# Main.net
KiCad netlist of a schematic drawn in Altium Designer
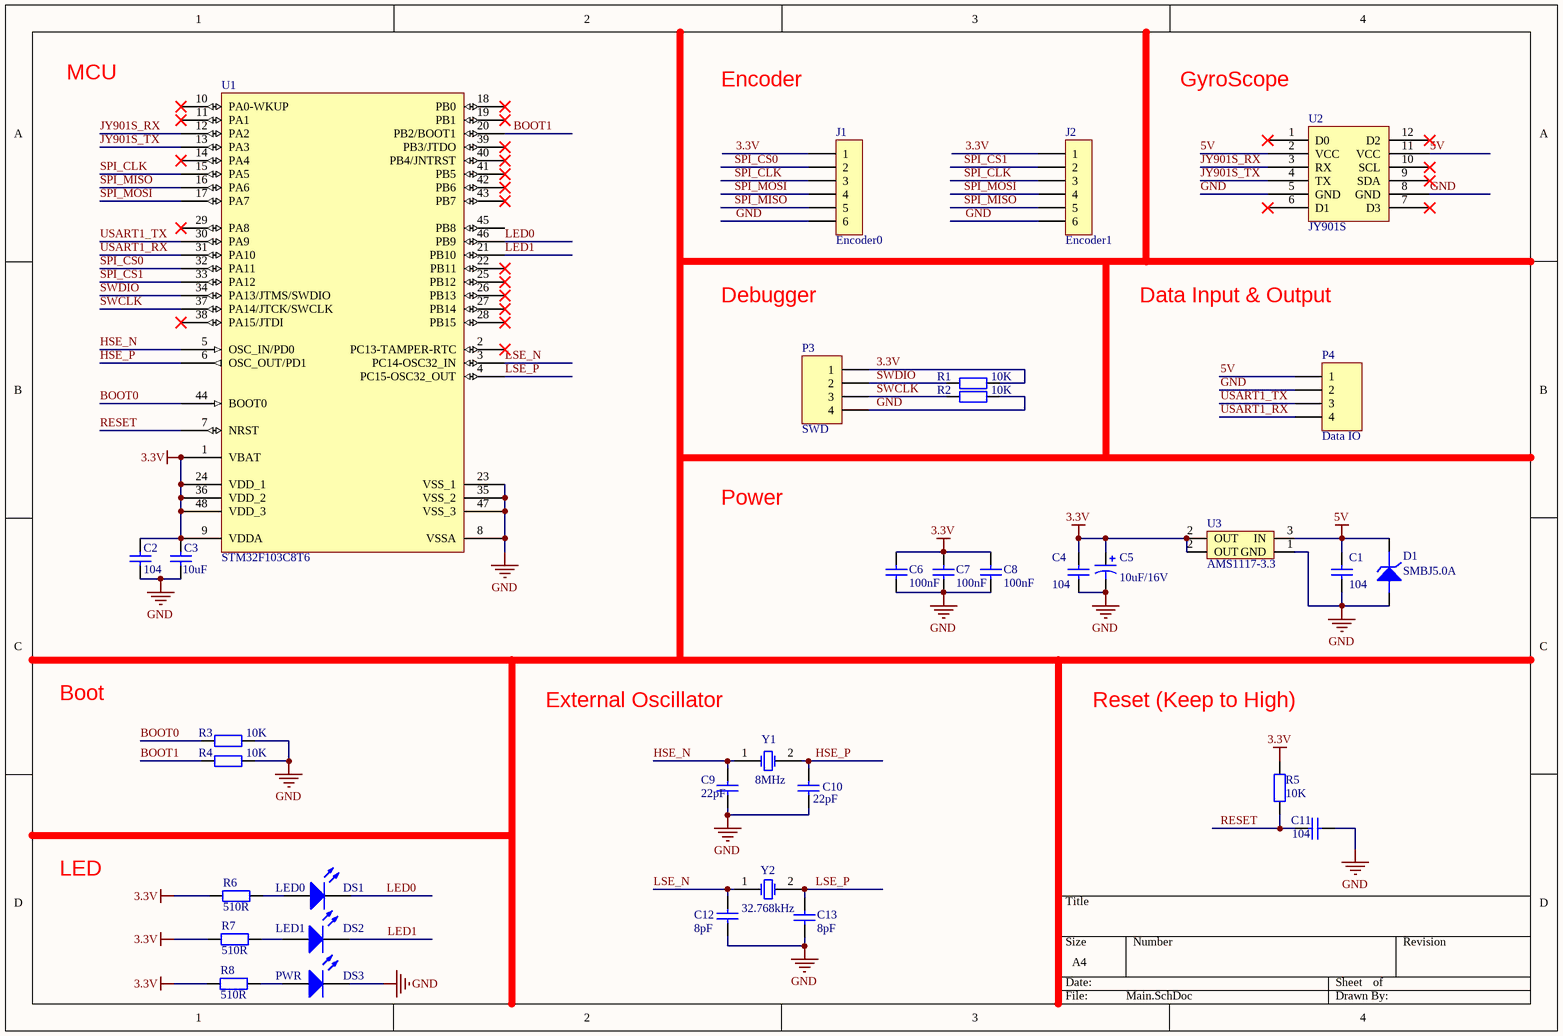
[diagram p0: Main.SchDoc]

(export (version "E")
  (design (tool "Eeschema 10.0.6"))
  (components
    (comp (ref "C1")
      (value "104")
      (footprint "0603C")
      (description "Capacitor")
      (fields (field (name "PUBLISHER") "Altium Limited"))
      (libsource (lib "prj-schlib") (part "Cap"))
    )
    (comp (ref "C2")
      (value "104")
      (footprint "0603C")
      (description "Capacitor")
      (fields (field (name "PUBLISHER") "Altium Limited"))
      (libsource (lib "prj-schlib") (part "Cap"))
    )
    (comp (ref "C3")
      (value "10uF")
      (footprint "0603C")
      (description "Capacitor")
      (fields (field (name "PUBLISHER") "Altium Limited"))
      (libsource (lib "prj-schlib") (part "Cap"))
    )
    (comp (ref "C4")
      (value "104")
      (footprint "0603C")
      (description "Capacitor")
      (fields (field (name "PUBLISHER") "Altium Limited"))
      (libsource (lib "prj-schlib") (part "Cap"))
    )
    (comp (ref "C5")
      (value "10uF/16V")
      (footprint "TAJ-A/3216")
      (description "Polarized Capacitor (Radial)")
      (fields (field (name "Comment") "Capacitor") (field (name "PUBLISHER") "Altium Limited"))
      (libsource (lib "prj-schlib") (part "Cap Pol1"))
    )
    (comp (ref "C6")
      (value "100nF")
      (footprint "0603C")
      (description "Capacitor")
      (fields (field (name "PUBLISHER") "Altium Limited"))
      (libsource (lib "prj-schlib") (part "Cap"))
    )
    (comp (ref "C7")
      (value "100nF")
      (footprint "0603C")
      (description "Capacitor")
      (fields (field (name "PUBLISHER") "Altium Limited"))
      (libsource (lib "prj-schlib") (part "Cap"))
    )
    (comp (ref "C8")
      (value "100nF")
      (footprint "0603C")
      (description "Capacitor")
      (fields (field (name "PUBLISHER") "Altium Limited"))
      (libsource (lib "prj-schlib") (part "Cap"))
    )
    (comp (ref "C9")
      (value "22pF")
      (footprint "0603C")
      (description "Capacitor")
      (fields (field (name "PUBLISHER") "Altium Limited"))
      (libsource (lib "prj-schlib") (part "Cap"))
    )
    (comp (ref "C10")
      (value "22pF")
      (footprint "0603C")
      (description "Capacitor")
      (fields (field (name "PUBLISHER") "Altium Limited"))
      (libsource (lib "prj-schlib") (part "Cap"))
    )
    (comp (ref "C11")
      (value "104")
      (footprint "0603C")
      (description "Capacitor")
      (fields (field (name "PUBLISHER") "Altium Limited"))
      (libsource (lib "prj-schlib") (part "Cap"))
    )
    (comp (ref "C12")
      (value "8pF")
      (footprint "0603C")
      (description "Capacitor")
      (fields (field (name "PUBLISHER") "Altium Limited"))
      (libsource (lib "prj-schlib") (part "Cap"))
    )
    (comp (ref "C13")
      (value "8pF")
      (footprint "0603C")
      (description "Capacitor")
      (fields (field (name "PUBLISHER") "Altium Limited"))
      (libsource (lib "prj-schlib") (part "Cap"))
    )
    (comp (ref "D1")
      (value "SMBJ5.0A")
      (footprint "SMB/DO-214AA")
      (description "稳压二极管")
      (fields (field (name "Comment") "TVS Diode"))
      (libsource (lib "prj-schlib") (part "DIODE ZENER"))
    )
    (comp (ref "DS1")
      (value "LED0")
      (footprint "LED-0805R")
      (description "Typical RED GaAs LED")
      (fields (field (name "PUBLISHER") "Altium Limited"))
      (libsource (lib "prj-schlib") (part "LED1"))
    )
    (comp (ref "DS2")
      (value "LED1")
      (footprint "LED-0805R")
      (description "Typical RED GaAs LED")
      (fields (field (name "PUBLISHER") "Altium Limited"))
      (libsource (lib "prj-schlib") (part "LED1"))
    )
    (comp (ref "DS3")
      (value "PWR")
      (footprint "LED-0805R")
      (description "Typical RED GaAs LED")
      (fields (field (name "PUBLISHER") "Altium Limited"))
      (libsource (lib "prj-schlib") (part "LED1"))
    )
    (comp (ref "J1") (value "Encoder0") (footprint "6P_SMD") (libsource (lib "prj-schlib") (part "Header 6")))
    (comp (ref "J2") (value "Encoder1") (footprint "6P_SMD") (libsource (lib "prj-schlib") (part "Header 6")))
    (comp (ref "P3")
      (value "SWD")
      (footprint "Pin HDR1X4/2.54mm-S")
      (description "Header, 4-Pin")
      (fields (field (name "PUBLISHER") "Altium Limited"))
      (libsource (lib "prj-schlib") (part "Header 4"))
    )
    (comp (ref "P4")
      (value "Data IO")
      (footprint "XH4/2.54mm/180")
      (description "Header, 4-Pin")
      (fields (field (name "PUBLISHER") "Altium Limited"))
      (libsource (lib "") (part "Header 4_1"))
    )
    (comp (ref "R1")
      (value "10K")
      (footprint "0603R")
      (description "Resistor")
      (fields (field (name "PUBLISHER") "Altium Limited"))
      (libsource (lib "prj-schlib") (part "Res2"))
    )
    (comp (ref "R2")
      (value "10K")
      (footprint "0603R")
      (description "Resistor")
      (fields (field (name "PUBLISHER") "Altium Limited"))
      (libsource (lib "prj-schlib") (part "Res2"))
    )
    (comp (ref "R3")
      (value "10K")
      (footprint "0603R")
      (description "Resistor")
      (fields (field (name "PUBLISHER") "Altium Limited"))
      (libsource (lib "") (part "Res2_1"))
    )
    (comp (ref "R4")
      (value "10K")
      (footprint "0603R")
      (description "Resistor")
      (fields (field (name "PUBLISHER") "Altium Limited"))
      (libsource (lib "") (part "Res2_1"))
    )
    (comp (ref "R5")
      (value "10K")
      (footprint "0603R")
      (description "Resistor")
      (fields (field (name "PUBLISHER") "Altium Limited"))
      (libsource (lib "") (part "Res2_2"))
    )
    (comp (ref "R6")
      (value "510R")
      (footprint "0603R")
      (description "Resistor")
      (fields (field (name "PUBLISHER") "Altium Limited"))
      (libsource (lib "prj-schlib") (part "Res2"))
    )
    (comp (ref "R7")
      (value "510R")
      (footprint "0603R")
      (description "Resistor")
      (fields (field (name "PUBLISHER") "Altium Limited"))
      (libsource (lib "prj-schlib") (part "Res2"))
    )
    (comp (ref "R8")
      (value "510R")
      (footprint "0603R")
      (description "Resistor")
      (fields (field (name "PUBLISHER") "Altium Limited"))
      (libsource (lib "prj-schlib") (part "Res2"))
    )
    (comp (ref "U1")
      (value "STM32F103C8T6")
      (footprint "LQFP48 7X7")
      (fields (field (name "Comment") "ST MCU LQFP48"))
      (libsource (lib "prj-schlib") (part "STM32F103C8T6"))
    )
    (comp (ref "U2") (value "JY901S") (footprint "JY901S") (libsource (lib "prj-schlib") (part "JY901S")))
    (comp (ref "U3")
      (value "AMS1117-3.3")
      (footprint "SOT223")
      (libsource (lib "prj-schlib") (part "AMS1117"))
    )
    (comp (ref "Y1")
      (value "8MHz")
      (footprint "OSC 5032-2P")
      (description "Crystal Oscillator")
      (fields (field (name "PUBLISHER") "*"))
      (libsource (lib "prj-schlib") (part "XTAL"))
    )
    (comp (ref "Y2")
      (value "32.768kHz")
      (footprint "OSC 3215-2P")
      (description "Crystal Oscillator")
      (fields (field (name "PUBLISHER") "*"))
      (libsource (lib "prj-schlib") (part "XTAL"))
    )
  )
  (nets
    (net (code "1") (name "/BOOT0") (class "Default")
      (node (ref "R3") (pin "2") (pinfunction "2_2") (pintype "passive"))
      (node (ref "U1") (pin "44") (pinfunction "BOOT0_44") (pintype "input"))
    )
    (net (code "2") (name "/BOOT1") (class "Default")
      (node (ref "R4") (pin "2") (pinfunction "2_2") (pintype "passive"))
      (node (ref "U1") (pin "20") (pinfunction "PB2/BOOT1_20") (pintype "bidirectional"))
    )
    (net (code "3") (name "/HSE_N") (class "Default")
      (node (ref "C9") (pin "2") (pinfunction "2_2") (pintype "passive"))
      (node (ref "U1") (pin "5") (pinfunction "OSC_IN/PD0_5") (pintype "input"))
      (node (ref "Y1") (pin "1") (pinfunction "OSC1_1") (pintype "passive"))
    )
    (net (code "4") (name "/HSE_P") (class "Default")
      (node (ref "C10") (pin "2") (pinfunction "2_2") (pintype "passive"))
      (node (ref "U1") (pin "6") (pinfunction "OSC_OUT/PD1_6") (pintype "output"))
      (node (ref "Y1") (pin "2") (pinfunction "OSC2_2") (pintype "passive"))
    )
    (net (code "5") (name "/JY901S_RX") (class "Default")
      (node (ref "U1") (pin "12") (pinfunction "PA2_12") (pintype "bidirectional"))
      (node (ref "U2") (pin "3") (pinfunction "RX_3") (pintype "passive"))
    )
    (net (code "6") (name "/JY901S_TX") (class "Default")
      (node (ref "U1") (pin "13") (pinfunction "PA3_13") (pintype "bidirectional"))
      (node (ref "U2") (pin "4") (pinfunction "TX_4") (pintype "passive"))
    )
    (net (code "7") (name "/LED0") (class "Default")
      (node (ref "DS1") (pin "2") (pinfunction "K_2") (pintype "passive"))
      (node (ref "U1") (pin "46") (pinfunction "PB9_46") (pintype "bidirectional"))
    )
    (net (code "8") (name "/LED1") (class "Default")
      (node (ref "DS2") (pin "2") (pinfunction "K_2") (pintype "passive"))
      (node (ref "U1") (pin "21") (pinfunction "PB10_21") (pintype "bidirectional"))
    )
    (net (code "9") (name "/LSE_N") (class "Default")
      (node (ref "C12") (pin "2") (pinfunction "2_2") (pintype "passive"))
      (node (ref "U1") (pin "3") (pinfunction "PC14-OSC32_IN_3") (pintype "bidirectional"))
      (node (ref "Y2") (pin "1") (pinfunction "OSC1_1") (pintype "passive"))
    )
    (net (code "10") (name "/LSE_P") (class "Default")
      (node (ref "C13") (pin "2") (pinfunction "2_2") (pintype "passive"))
      (node (ref "U1") (pin "4") (pinfunction "PC15-OSC32_OUT_4") (pintype "bidirectional"))
      (node (ref "Y2") (pin "2") (pinfunction "OSC2_2") (pintype "passive"))
    )
    (net (code "11") (name "/RESET") (class "Default")
      (node (ref "C11") (pin "2") (pinfunction "2_2") (pintype "passive"))
      (node (ref "R5") (pin "2") (pinfunction "2_2") (pintype "passive"))
      (node (ref "U1") (pin "7") (pinfunction "NRST_7") (pintype "bidirectional"))
    )
    (net (code "12") (name "/SPI_CLK") (class "Default")
      (node (ref "J1") (pin "3") (pinfunction "3_3") (pintype "passive"))
      (node (ref "J2") (pin "3") (pinfunction "3_3") (pintype "passive"))
      (node (ref "U1") (pin "15") (pinfunction "PA5_15") (pintype "bidirectional"))
    )
    (net (code "13") (name "/SPI_CS0") (class "Default")
      (node (ref "J1") (pin "2") (pinfunction "2_2") (pintype "passive"))
      (node (ref "U1") (pin "32") (pinfunction "PA11_32") (pintype "bidirectional"))
    )
    (net (code "14") (name "/SPI_CS1") (class "Default")
      (node (ref "J2") (pin "2") (pinfunction "2_2") (pintype "passive"))
      (node (ref "U1") (pin "33") (pinfunction "PA12_33") (pintype "bidirectional"))
    )
    (net (code "15") (name "/SPI_MISO") (class "Default")
      (node (ref "J1") (pin "5") (pinfunction "5_5") (pintype "passive"))
      (node (ref "J2") (pin "5") (pinfunction "5_5") (pintype "passive"))
      (node (ref "U1") (pin "16") (pinfunction "PA6_16") (pintype "bidirectional"))
    )
    (net (code "16") (name "/SPI_MOSI") (class "Default")
      (node (ref "J1") (pin "4") (pinfunction "4_4") (pintype "passive"))
      (node (ref "J2") (pin "4") (pinfunction "4_4") (pintype "passive"))
      (node (ref "U1") (pin "17") (pinfunction "PA7_17") (pintype "bidirectional"))
    )
    (net (code "17") (name "/SWCLK") (class "Default")
      (node (ref "P3") (pin "3") (pinfunction "3_3") (pintype "passive"))
      (node (ref "R2") (pin "1") (pinfunction "1_1") (pintype "passive"))
      (node (ref "U1") (pin "37") (pinfunction "PA14/JTCK/SWCLK_37") (pintype "bidirectional"))
    )
    (net (code "18") (name "/SWDIO") (class "Default")
      (node (ref "P3") (pin "2") (pinfunction "2_2") (pintype "passive"))
      (node (ref "R1") (pin "1") (pinfunction "1_1") (pintype "passive"))
      (node (ref "U1") (pin "34") (pinfunction "PA13/JTMS/SWDIO_34") (pintype "bidirectional"))
    )
    (net (code "19") (name "/USART1_RX") (class "Default")
      (node (ref "P4") (pin "4") (pinfunction "4_4") (pintype "passive"))
      (node (ref "U1") (pin "31") (pinfunction "PA10_31") (pintype "bidirectional"))
    )
    (net (code "20") (name "/USART1_TX") (class "Default")
      (node (ref "P4") (pin "3") (pinfunction "3_3") (pintype "passive"))
      (node (ref "U1") (pin "30") (pinfunction "PA9_30") (pintype "bidirectional"))
    )
    (net (code "21") (name "3.3V") (class "Default")
      (node (ref "C2") (pin "2") (pinfunction "2_2") (pintype "passive"))
      (node (ref "C3") (pin "2") (pinfunction "2_2") (pintype "passive"))
      (node (ref "C4") (pin "2") (pinfunction "2_2") (pintype "passive"))
      (node (ref "C5") (pin "1") (pinfunction "1_1") (pintype "passive"))
      (node (ref "C6") (pin "2") (pinfunction "2_2") (pintype "passive"))
      (node (ref "C7") (pin "2") (pinfunction "2_2") (pintype "passive"))
      (node (ref "C8") (pin "2") (pinfunction "2_2") (pintype "passive"))
      (node (ref "J1") (pin "1") (pinfunction "1_1") (pintype "passive"))
      (node (ref "J2") (pin "1") (pinfunction "1_1") (pintype "passive"))
      (node (ref "P3") (pin "1") (pinfunction "1_1") (pintype "passive"))
      (node (ref "R1") (pin "2") (pinfunction "2_2") (pintype "passive"))
      (node (ref "R5") (pin "1") (pinfunction "1_1") (pintype "passive"))
      (node (ref "R6") (pin "1") (pinfunction "1_1") (pintype "passive"))
      (node (ref "R7") (pin "1") (pinfunction "1_1") (pintype "passive"))
      (node (ref "R8") (pin "1") (pinfunction "1_1") (pintype "passive"))
      (node (ref "U1") (pin "1") (pinfunction "VBAT_1") (pintype "power_in"))
      (node (ref "U1") (pin "24") (pinfunction "VDD_1_24") (pintype "power_in"))
      (node (ref "U1") (pin "36") (pinfunction "VDD_2_36") (pintype "power_in"))
      (node (ref "U1") (pin "48") (pinfunction "VDD_3_48") (pintype "power_in"))
      (node (ref "U1") (pin "9") (pinfunction "VDDA_9") (pintype "power_in"))
      (node (ref "U3") (pin "2") (pinfunction "OUT_2") (pintype "passive"))
    )
    (net (code "22") (name "5V") (class "Default")
      (node (ref "C1") (pin "2") (pinfunction "2_2") (pintype "passive"))
      (node (ref "D1") (pin "K") (pinfunction "K_K") (pintype "passive"))
      (node (ref "P4") (pin "1") (pinfunction "1_1") (pintype "passive"))
      (node (ref "U2") (pin "11") (pinfunction "VCC_11") (pintype "passive"))
      (node (ref "U2") (pin "2") (pinfunction "VCC_2") (pintype "passive"))
      (node (ref "U3") (pin "3") (pinfunction "IN_3") (pintype "passive"))
    )
    (net (code "23") (name "GND") (class "Default")
      (node (ref "C1") (pin "1") (pinfunction "1_1") (pintype "passive"))
      (node (ref "C10") (pin "1") (pinfunction "1_1") (pintype "passive"))
      (node (ref "C11") (pin "1") (pinfunction "1_1") (pintype "passive"))
      (node (ref "C12") (pin "1") (pinfunction "1_1") (pintype "passive"))
      (node (ref "C13") (pin "1") (pinfunction "1_1") (pintype "passive"))
      (node (ref "C2") (pin "1") (pinfunction "1_1") (pintype "passive"))
      (node (ref "C3") (pin "1") (pinfunction "1_1") (pintype "passive"))
      (node (ref "C4") (pin "1") (pinfunction "1_1") (pintype "passive"))
      (node (ref "C5") (pin "2") (pinfunction "2_2") (pintype "passive"))
      (node (ref "C6") (pin "1") (pinfunction "1_1") (pintype "passive"))
      (node (ref "C7") (pin "1") (pinfunction "1_1") (pintype "passive"))
      (node (ref "C8") (pin "1") (pinfunction "1_1") (pintype "passive"))
      (node (ref "C9") (pin "1") (pinfunction "1_1") (pintype "passive"))
      (node (ref "D1") (pin "A") (pinfunction "A_A") (pintype "passive"))
      (node (ref "DS3") (pin "2") (pinfunction "K_2") (pintype "passive"))
      (node (ref "J1") (pin "6") (pinfunction "6_6") (pintype "passive"))
      (node (ref "J2") (pin "6") (pinfunction "6_6") (pintype "passive"))
      (node (ref "P3") (pin "4") (pinfunction "4_4") (pintype "passive"))
      (node (ref "P4") (pin "2") (pinfunction "2_2") (pintype "passive"))
      (node (ref "R2") (pin "2") (pinfunction "2_2") (pintype "passive"))
      (node (ref "R3") (pin "1") (pinfunction "1_1") (pintype "passive"))
      (node (ref "R4") (pin "1") (pinfunction "1_1") (pintype "passive"))
      (node (ref "U1") (pin "23") (pinfunction "VSS_1_23") (pintype "power_in"))
      (node (ref "U1") (pin "35") (pinfunction "VSS_2_35") (pintype "power_in"))
      (node (ref "U1") (pin "47") (pinfunction "VSS_3_47") (pintype "power_in"))
      (node (ref "U1") (pin "8") (pinfunction "VSSA_8") (pintype "power_in"))
      (node (ref "U2") (pin "5") (pinfunction "GND_5") (pintype "passive"))
      (node (ref "U2") (pin "8") (pinfunction "GND_8") (pintype "passive"))
      (node (ref "U3") (pin "1") (pinfunction "GND_1") (pintype "passive"))
    )
    (net (code "24") (name "Net-(DS1-A)") (class "Default")
      (node (ref "DS1") (pin "1") (pinfunction "A_1") (pintype "passive"))
      (node (ref "R6") (pin "2") (pinfunction "2_2") (pintype "passive"))
    )
    (net (code "25") (name "Net-(DS2-A)") (class "Default")
      (node (ref "DS2") (pin "1") (pinfunction "A_1") (pintype "passive"))
      (node (ref "R7") (pin "2") (pinfunction "2_2") (pintype "passive"))
    )
    (net (code "26") (name "Net-(DS3-A)") (class "Default")
      (node (ref "DS3") (pin "1") (pinfunction "A_1") (pintype "passive"))
      (node (ref "R8") (pin "2") (pinfunction "2_2") (pintype "passive"))
    )
    (net (code "27") (name "unconnected-(U1-PA0-WKUP-Pad10)") (class "Default")
      (node (ref "U1") (pin "10") (pinfunction "PA0-WKUP_10") (pintype "bidirectional+no_connect"))
    )
    (net (code "28") (name "unconnected-(U1-PA1-Pad11)") (class "Default")
      (node (ref "U1") (pin "11") (pinfunction "PA1_11") (pintype "bidirectional+no_connect"))
    )
    (net (code "29") (name "unconnected-(U1-PA4-Pad14)") (class "Default")
      (node (ref "U1") (pin "14") (pinfunction "PA4_14") (pintype "bidirectional+no_connect"))
    )
    (net (code "30") (name "unconnected-(U1-PA8-Pad29)") (class "Default")
      (node (ref "U1") (pin "29") (pinfunction "PA8_29") (pintype "bidirectional+no_connect"))
    )
    (net (code "31") (name "unconnected-(U1-PA15{slash}JTDI-Pad38)") (class "Default")
      (node (ref "U1") (pin "38") (pinfunction "PA15/JTDI_38") (pintype "bidirectional+no_connect"))
    )
    (net (code "32") (name "unconnected-(U1-PB0-Pad18)") (class "Default")
      (node (ref "U1") (pin "18") (pinfunction "PB0_18") (pintype "bidirectional+no_connect"))
    )
    (net (code "33") (name "unconnected-(U1-PB1-Pad19)") (class "Default")
      (node (ref "U1") (pin "19") (pinfunction "PB1_19") (pintype "bidirectional+no_connect"))
    )
    (net (code "34") (name "unconnected-(U1-PB3{slash}JTDO-Pad39)") (class "Default")
      (node (ref "U1") (pin "39") (pinfunction "PB3/JTDO_39") (pintype "bidirectional+no_connect"))
    )
    (net (code "35") (name "unconnected-(U1-PB4{slash}JNTRST-Pad40)") (class "Default")
      (node (ref "U1") (pin "40") (pinfunction "PB4/JNTRST_40") (pintype "bidirectional+no_connect"))
    )
    (net (code "36") (name "unconnected-(U1-PB5-Pad41)") (class "Default")
      (node (ref "U1") (pin "41") (pinfunction "PB5_41") (pintype "bidirectional+no_connect"))
    )
    (net (code "37") (name "unconnected-(U1-PB6-Pad42)") (class "Default")
      (node (ref "U1") (pin "42") (pinfunction "PB6_42") (pintype "bidirectional+no_connect"))
    )
    (net (code "38") (name "unconnected-(U1-PB7-Pad43)") (class "Default")
      (node (ref "U1") (pin "43") (pinfunction "PB7_43") (pintype "bidirectional+no_connect"))
    )
    (net (code "39") (name "unconnected-(U1-PB8-Pad45)") (class "Default")
      (node (ref "U1") (pin "45") (pinfunction "PB8_45") (pintype "bidirectional"))
    )
    (net (code "40") (name "unconnected-(U1-PB11-Pad22)") (class "Default")
      (node (ref "U1") (pin "22") (pinfunction "PB11_22") (pintype "bidirectional+no_connect"))
    )
    (net (code "41") (name "unconnected-(U1-PB12-Pad25)") (class "Default")
      (node (ref "U1") (pin "25") (pinfunction "PB12_25") (pintype "bidirectional+no_connect"))
    )
    (net (code "42") (name "unconnected-(U1-PB13-Pad26)") (class "Default")
      (node (ref "U1") (pin "26") (pinfunction "PB13_26") (pintype "bidirectional+no_connect"))
    )
    (net (code "43") (name "unconnected-(U1-PB14-Pad27)") (class "Default")
      (node (ref "U1") (pin "27") (pinfunction "PB14_27") (pintype "bidirectional+no_connect"))
    )
    (net (code "44") (name "unconnected-(U1-PB15-Pad28)") (class "Default")
      (node (ref "U1") (pin "28") (pinfunction "PB15_28") (pintype "bidirectional+no_connect"))
    )
    (net (code "45") (name "unconnected-(U1-PC13-TAMPER-RTC-Pad2)") (class "Default")
      (node (ref "U1") (pin "2") (pinfunction "PC13-TAMPER-RTC_2") (pintype "bidirectional+no_connect"))
    )
    (net (code "46") (name "unconnected-(U2-D0-Pad1)") (class "Default")
      (node (ref "U2") (pin "1") (pinfunction "D0_1") (pintype "passive+no_connect"))
    )
    (net (code "47") (name "unconnected-(U2-D1-Pad6)") (class "Default")
      (node (ref "U2") (pin "6") (pinfunction "D1_6") (pintype "passive+no_connect"))
    )
    (net (code "48") (name "unconnected-(U2-D2-Pad12)") (class "Default")
      (node (ref "U2") (pin "12") (pinfunction "D2_12") (pintype "passive+no_connect"))
    )
    (net (code "49") (name "unconnected-(U2-D3-Pad7)") (class "Default")
      (node (ref "U2") (pin "7") (pinfunction "D3_7") (pintype "passive+no_connect"))
    )
    (net (code "50") (name "unconnected-(U2-SCL-Pad10)") (class "Default")
      (node (ref "U2") (pin "10") (pinfunction "SCL_10") (pintype "passive+no_connect"))
    )
    (net (code "51") (name "unconnected-(U2-SDA-Pad9)") (class "Default")
      (node (ref "U2") (pin "9") (pinfunction "SDA_9") (pintype "passive+no_connect"))
    )
  )
)
